# Sensor_board_2024.net
KiCad netlist of a schematic drawn in EAGLE
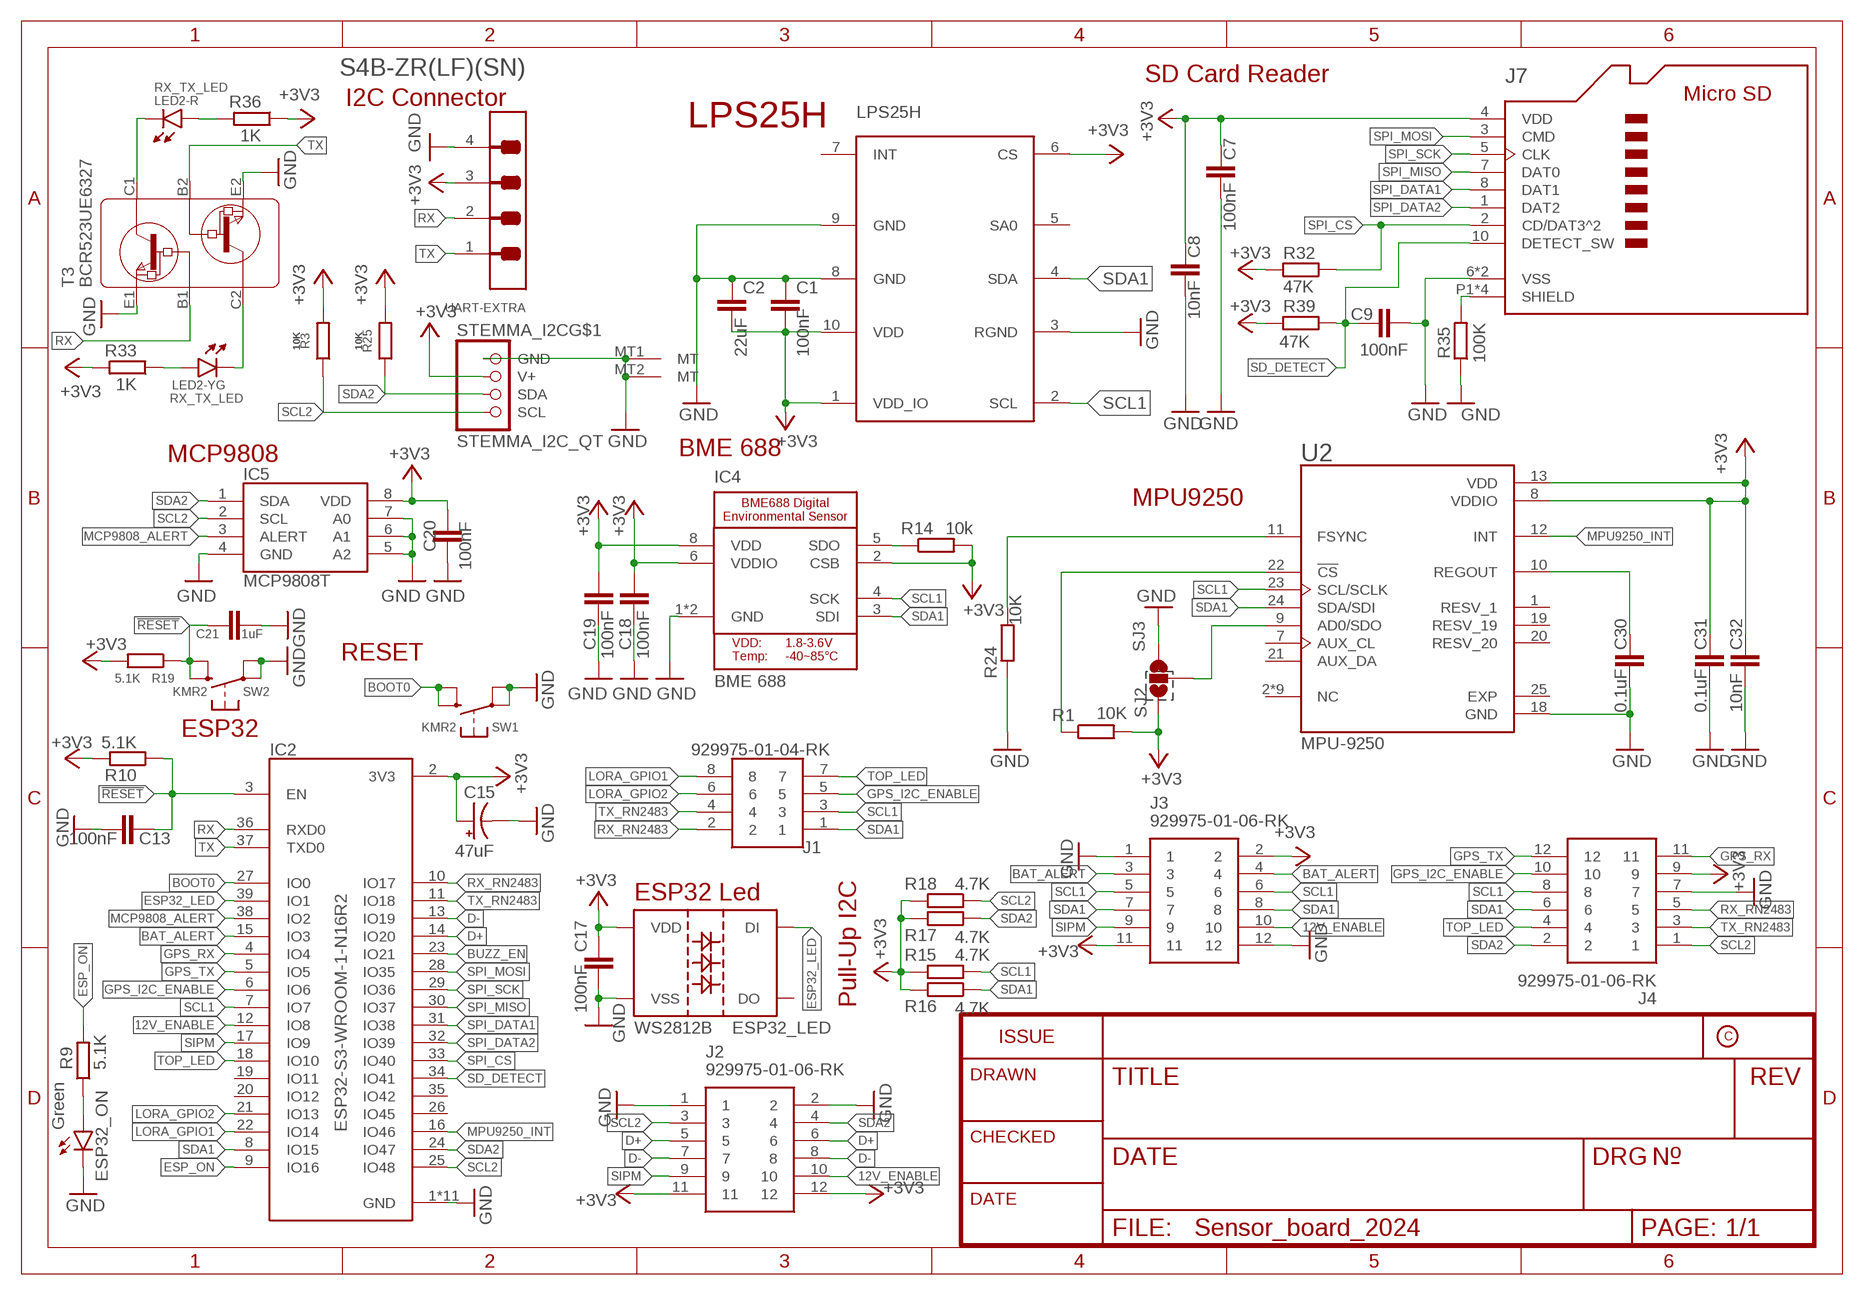
[diagram p0: schematic, sheet 1]

(export (version "E")
  (design (tool "Eeschema 10.0.6"))
  (components
    (comp (ref "C1")
      (value "100nF")
      (footprint "eagle-import:C0603")
      (libsource (lib "eagle-import") (part "C-EUC0603"))
    )
    (comp (ref "C2")
      (value "22uF")
      (footprint "eagle-import:C0603")
      (libsource (lib "eagle-import") (part "C-EUC0603"))
    )
    (comp (ref "C7")
      (value "100nF")
      (footprint "eagle-import:C0603")
      (libsource (lib "eagle-import") (part "C-EUC0603"))
    )
    (comp (ref "C8")
      (value "10nF")
      (footprint "eagle-import:C0603")
      (libsource (lib "eagle-import") (part "C-EUC0603"))
    )
    (comp (ref "C9")
      (value "100nF")
      (footprint "eagle-import:C0603")
      (libsource (lib "eagle-import") (part "C-EUC0603"))
    )
    (comp (ref "C13")
      (value "100nF")
      (footprint "eagle-import:C0603")
      (libsource (lib "eagle-import") (part "C-EUC0603"))
    )
    (comp (ref "C15")
      (value "47uF")
      (footprint "eagle-import:CAPMP6032X250N")
      (fields (field (name "MF") "Vishay") (field (name "MP") "293D226X9025C2TE3"))
      (libsource (lib "eagle-import") (part "293D226X9025C2TE3"))
    )
    (comp (ref "C17")
      (value "100nF")
      (footprint "eagle-import:C0603")
      (libsource (lib "eagle-import") (part "C-EUC0603"))
    )
    (comp (ref "C18")
      (value "100nF")
      (footprint "eagle-import:C0603")
      (libsource (lib "eagle-import") (part "C-EUC0603"))
    )
    (comp (ref "C19")
      (value "100nF")
      (footprint "eagle-import:C0603")
      (libsource (lib "eagle-import") (part "C-EUC0603"))
    )
    (comp (ref "C20")
      (value "100nF")
      (footprint "eagle-import:C0603")
      (libsource (lib "eagle-import") (part "C-EUC0603"))
    )
    (comp (ref "C21")
      (value "1uF")
      (footprint "eagle-import:C0603")
      (libsource (lib "eagle-import") (part "C-EUC0603"))
    )
    (comp (ref "C30")
      (value "0.1uF")
      (footprint "eagle-import:0603-CAP")
      (libsource (lib "eagle-import") (part "0.1UF-25V(+80/-20%)(0603)"))
    )
    (comp (ref "C31")
      (value "0.1uF")
      (footprint "eagle-import:0603-CAP")
      (libsource (lib "eagle-import") (part "0.1UF-25V(+80/-20%)(0603)"))
    )
    (comp (ref "C32")
      (value "10nF")
      (footprint "eagle-import:0603-CAP")
      (libsource (lib "eagle-import") (part "0.1UF-25V(+80/-20%)(0603)"))
    )
    (comp (ref "ESP32_LED")
      (value "WS2812B")
      (footprint "eagle-import:WS2812B")
      (libsource (lib "eagle-import") (part "WS2812B"))
    )
    (comp (ref "ESP32_ON")
      (value "Green")
      (footprint "eagle-import:CHIPLED_0805")
      (libsource (lib "eagle-import") (part "LEDCHIPLED_0805"))
    )
    (comp (ref "IC2")
      (value "ESP32-S3-WROOM-1-N16R2")
      (footprint "eagle-import:XCVR_ESP32-S3-WROOM-1-N16R2")
      (fields (field (name "MF") "Espressif Systems") (field (name "SPICEPREFIX") "X"))
      (libsource (lib "eagle-import") (part "ESP32-S3-WROOM-1-N16R2"))
    )
    (comp (ref "IC4")
      (value "BME 688")
      (footprint "eagle-import:BME_688")
      (libsource (lib "eagle-import") (part "BME_688_V1"))
    )
    (comp (ref "IC5")
      (value "MCP9808T")
      (footprint "eagle-import:SOP65P490X110-8N")
      (fields
        (field (name "MANUFACTURER_PART_NUMBER") "MCP9808T-E/MS")
        (field (name "MOUSER_PART_NUMBER") "579-MCP9808T-E/MS")
      )
      (libsource (lib "eagle-import") (part "MCP9808T-E_MS"))
    )
    (comp (ref "J1")
      (value "929975-01-04-RK")
      (footprint "eagle-import:RHDR8W76P254_2X4_1016X508X839P")
      (fields (field (name "MOUSER_PART_NUMBER") "517-929975-01-04-RK"))
      (libsource (lib "eagle-import") (part "929975-01-04-RK"))
    )
    (comp (ref "J2")
      (value "929975-01-06-RK")
      (footprint "eagle-import:RHDR12W76P254_2X6_1524X508X839")
      (fields (field (name "MOUSER_PART_NUMBER") "517-929975-01-06-RK"))
      (libsource (lib "eagle-import") (part "929975-01-06-RK"))
    )
    (comp (ref "J3")
      (value "929975-01-06-RK")
      (footprint "eagle-import:RHDR12W76P254_2X6_1524X508X839")
      (fields (field (name "MOUSER_PART_NUMBER") "517-929975-01-06-RK"))
      (libsource (lib "eagle-import") (part "929975-01-06-RK"))
    )
    (comp (ref "J4")
      (value "929975-01-06-RK")
      (footprint "eagle-import:RHDR12W76P254_2X6_1524X508X839")
      (fields (field (name "MOUSER_PART_NUMBER") "517-929975-01-06-RK"))
      (libsource (lib "eagle-import") (part "929975-01-06-RK"))
    )
    (comp (ref "J7")
      (value "503398-1892")
      (footprint "eagle-import:MOLEX_503398-1892")
      (fields (field (name "MF") "Molex") (field (name "MP") "5033981892"))
      (libsource (lib "eagle-import") (part "503398-1892"))
    )
    (comp (ref "LED2")
      (value "RX_TX_LED")
      (footprint "eagle-import:3216(1206)-4")
      (fields (field (name "MF") "OptoSupply") (field (name "MP") "OSRG1206C1C"))
      (libsource (lib "eagle-import") (part "OSRG1206C1C"))
    )
    (comp (ref "LPS25H")
      (value "LPS25H")
      (footprint "eagle-import:LPS25H")
      (fields (field (name "MF") "STMicroelectronics"))
      (libsource (lib "eagle-import") (part "LPS25H"))
    )
    (comp (ref "R1")
      (value "10K")
      (footprint "eagle-import:R0603")
      (libsource (lib "eagle-import") (part "rcl_334_R-EU_R0603"))
    )
    (comp (ref "R3")
      (value "10K")
      (footprint "eagle-import:R0603")
      (libsource (lib "eagle-import") (part "rcl_334_R-EU_R0603"))
    )
    (comp (ref "R9")
      (value "5.1K")
      (footprint "eagle-import:R0603")
      (libsource (lib "eagle-import") (part "rcl_334_R-EU_R0603"))
    )
    (comp (ref "R10")
      (value "5.1K")
      (footprint "eagle-import:R0603")
      (libsource (lib "eagle-import") (part "rcl_334_R-EU_R0603"))
    )
    (comp (ref "R14")
      (value "10k")
      (footprint "eagle-import:R0603")
      (libsource (lib "eagle-import") (part "rcl_334_R-EU_R0603"))
    )
    (comp (ref "R15")
      (value "4.7K")
      (footprint "eagle-import:R0603")
      (libsource (lib "eagle-import") (part "rcl_334_R-EU_R0603"))
    )
    (comp (ref "R16")
      (value "4.7K")
      (footprint "eagle-import:R0603")
      (libsource (lib "eagle-import") (part "rcl_334_R-EU_R0603"))
    )
    (comp (ref "R17")
      (value "4.7K")
      (footprint "eagle-import:R0603")
      (libsource (lib "eagle-import") (part "rcl_334_R-EU_R0603"))
    )
    (comp (ref "R18")
      (value "4.7K")
      (footprint "eagle-import:R0603")
      (libsource (lib "eagle-import") (part "rcl_334_R-EU_R0603"))
    )
    (comp (ref "R19")
      (value "5.1K")
      (footprint "eagle-import:R0603")
      (libsource (lib "eagle-import") (part "rcl_334_R-EU_R0603"))
    )
    (comp (ref "R24")
      (value "10K")
      (footprint "eagle-import:R0603")
      (libsource (lib "eagle-import") (part "rcl_334_R-EU_R0603"))
    )
    (comp (ref "R25")
      (value "10K")
      (footprint "eagle-import:R0603")
      (libsource (lib "eagle-import") (part "rcl_334_R-EU_R0603"))
    )
    (comp (ref "R32")
      (value "47K")
      (footprint "eagle-import:R0603")
      (libsource (lib "eagle-import") (part "R-EU_R0603"))
    )
    (comp (ref "R33")
      (value "1K")
      (footprint "eagle-import:R0603")
      (libsource (lib "eagle-import") (part "R-EU_R0603"))
    )
    (comp (ref "R35")
      (value "100K")
      (footprint "eagle-import:R0603")
      (libsource (lib "eagle-import") (part "R-EU_R0603"))
    )
    (comp (ref "R36")
      (value "1K")
      (footprint "eagle-import:R0603")
      (libsource (lib "eagle-import") (part "R-EU_R0603"))
    )
    (comp (ref "R39")
      (value "47K")
      (footprint "eagle-import:R0603")
      (libsource (lib "eagle-import") (part "R-EU_R0603"))
    )
    (comp (ref "SJ2")
      (value "SJ3")
      (footprint "eagle-import:SPARKFUN_SJ_3")
      (libsource (lib "eagle-import") (part "SPARKFUN_SOLDERJUMPER_2WAYS"))
    )
    (comp (ref "STEMMA_I2C")
      (value "STEMMA_I2C_QT")
      (footprint "eagle-import:JST_SH4")
      (libsource (lib "eagle-import") (part "STEMMA_I2C_QT"))
    )
    (comp (ref "SW1")
      (value "KMR2")
      (footprint "eagle-import:BTN_KMR2_4.6X2.8")
      (libsource (lib "eagle-import") (part "SWITCH_TACT_SMT4.6X2.8"))
    )
    (comp (ref "SW2")
      (value "KMR2")
      (footprint "eagle-import:BTN_KMR2_4.6X2.8")
      (libsource (lib "eagle-import") (part "SWITCH_TACT_SMT4.6X2.8"))
    )
    (comp (ref "T3")
      (value "BCR523UE6327")
      (footprint "eagle-import:SOT-23")
      (fields (field (name "MPN") "DSS20201L-7"))
      (libsource (lib "eagle-import") (part "NPNSOT23"))
    )
    (comp (ref "U2")
      (value "MPU-9250")
      (footprint "eagle-import:QFN40P300X300X105-25N")
      (fields (field (name "MF") "TDK InvenSense"))
      (libsource (lib "eagle-import") (part "MPU-9250"))
    )
    (comp (ref "UART-EXTRA")
      (value "JST_S4B-ZR_LF")
      (footprint "eagle-import:JST_S4B-ZR_LF_SN_0")
      (fields
        (field (name "DIGIKEY_PART_NUMBER") "455-1671-ND")
        (field (name "MF") "JST")
        (field (name "MPN") "S4B-ZR(LF)(SN)")
      )
      (libsource (lib "eagle-import") (part "JST_S4B-ZR_LF_SNJST_S4B-ZR_LF_SN_0_0"))
    )
  )
  (nets
    (net (code "1") (name "+3V3") (class "Default")
      (node (ref "C1") (pin "2") (pinfunction "2_2") (pintype "passive"))
      (node (ref "C15") (pin "1") (pinfunction "+_1") (pintype "passive"))
      (node (ref "C17") (pin "1") (pinfunction "1_1") (pintype "passive"))
      (node (ref "C18") (pin "2") (pinfunction "2_2") (pintype "passive"))
      (node (ref "C19") (pin "2") (pinfunction "2_2") (pintype "passive"))
      (node (ref "C2") (pin "2") (pinfunction "2_2") (pintype "passive"))
      (node (ref "C20") (pin "2") (pinfunction "2_2") (pintype "passive"))
      (node (ref "C31") (pin "1") (pinfunction "1_1") (pintype "passive"))
      (node (ref "C32") (pin "1") (pinfunction "1_1") (pintype "passive"))
      (node (ref "C7") (pin "1") (pinfunction "1_1") (pintype "passive"))
      (node (ref "C8") (pin "1") (pinfunction "1_1") (pintype "passive"))
      (node (ref "ESP32_LED") (pin "1") (pinfunction "VDD_1") (pintype "bidirectional"))
      (node (ref "IC2") (pin "2") (pinfunction "3V3_2") (pintype "power_in"))
      (node (ref "IC4") (pin "2") (pinfunction "CSB_2") (pintype "input"))
      (node (ref "IC4") (pin "6") (pinfunction "VDDIO_6") (pintype "power_in"))
      (node (ref "IC4") (pin "8") (pinfunction "VDD_8") (pintype "power_in"))
      (node (ref "IC5") (pin "8") (pinfunction "VDD_8") (pintype "power_in"))
      (node (ref "J2") (pin "11") (pinfunction "11_11") (pintype "bidirectional"))
      (node (ref "J2") (pin "12") (pinfunction "12_12") (pintype "bidirectional"))
      (node (ref "J3") (pin "11") (pinfunction "11_11") (pintype "bidirectional"))
      (node (ref "J3") (pin "2") (pinfunction "2_2") (pintype "bidirectional"))
      (node (ref "J4") (pin "9") (pinfunction "9_9") (pintype "bidirectional"))
      (node (ref "J7") (pin "4") (pinfunction "VDD_4") (pintype "bidirectional"))
      (node (ref "LPS25H") (pin "1") (pinfunction "VDD_IO_1") (pintype "power_in"))
      (node (ref "LPS25H") (pin "10") (pinfunction "VDD_10") (pintype "power_in"))
      (node (ref "LPS25H") (pin "6") (pinfunction "CS_6") (pintype "bidirectional"))
      (node (ref "R1") (pin "2") (pinfunction "2_2") (pintype "passive"))
      (node (ref "R10") (pin "2") (pinfunction "2_2") (pintype "passive"))
      (node (ref "R14") (pin "2") (pinfunction "2_2") (pintype "passive"))
      (node (ref "R15") (pin "2") (pinfunction "2_2") (pintype "passive"))
      (node (ref "R16") (pin "2") (pinfunction "2_2") (pintype "passive"))
      (node (ref "R17") (pin "2") (pinfunction "2_2") (pintype "passive"))
      (node (ref "R18") (pin "2") (pinfunction "2_2") (pintype "passive"))
      (node (ref "R19") (pin "2") (pinfunction "2_2") (pintype "passive"))
      (node (ref "R25") (pin "2") (pinfunction "2_2") (pintype "passive"))
      (node (ref "R3") (pin "2") (pinfunction "2_2") (pintype "passive"))
      (node (ref "R32") (pin "2") (pinfunction "2_2") (pintype "passive"))
      (node (ref "R33") (pin "2") (pinfunction "2_2") (pintype "passive"))
      (node (ref "R36") (pin "1") (pinfunction "1_1") (pintype "passive"))
      (node (ref "R39") (pin "2") (pinfunction "2_2") (pintype "passive"))
      (node (ref "SJ2") (pin "1") (pinfunction "1_1") (pintype "passive"))
      (node (ref "STEMMA_I2C") (pin "2") (pinfunction "V+_2") (pintype "passive"))
      (node (ref "U2") (pin "13") (pinfunction "VDD_13") (pintype "power_in"))
      (node (ref "U2") (pin "8") (pinfunction "VDDIO_8") (pintype "power_in"))
      (node (ref "UART-EXTRA") (pin "3") (pinfunction "3_3") (pintype "passive"))
    )
    (net (code "2") (name "/RESV_1") (class "Default")
      (node (ref "U2") (pin "1") (pinfunction "RESV_1_1") (pintype "power_in"))
    )
    (net (code "3") (name "/RESV_20") (class "Default")
      (node (ref "U2") (pin "20") (pinfunction "RESV_20_20") (pintype "power_in"))
    )
    (net (code "4") (name "/~{RESET}") (class "Default")
      (node (ref "C13") (pin "1") (pinfunction "1_1") (pintype "passive"))
      (node (ref "C21") (pin "1") (pinfunction "1_1") (pintype "passive"))
      (node (ref "IC2") (pin "3") (pinfunction "EN_3") (pintype "input"))
      (node (ref "R10") (pin "1") (pinfunction "1_1") (pintype "passive"))
      (node (ref "R19") (pin "1") (pinfunction "1_1") (pintype "passive"))
      (node (ref "SW2") (pin "B") (pinfunction "S_B") (pintype "passive"))
      (node (ref "SW2") (pin "B'") (pinfunction "S1_B'") (pintype "passive"))
    )
    (net (code "5") (name "12V_ENABLE") (class "Default")
      (node (ref "IC2") (pin "12") (pinfunction "IO8_12") (pintype "bidirectional"))
      (node (ref "J2") (pin "10") (pinfunction "10_10") (pintype "bidirectional"))
      (node (ref "J3") (pin "10") (pinfunction "10_10") (pintype "bidirectional"))
    )
    (net (code "6") (name "BAT_ALERT") (class "Default")
      (node (ref "IC2") (pin "15") (pinfunction "IO3_15") (pintype "bidirectional"))
      (node (ref "J3") (pin "3") (pinfunction "3_3") (pintype "bidirectional"))
      (node (ref "J3") (pin "4") (pinfunction "4_4") (pintype "bidirectional"))
    )
    (net (code "7") (name "BOOT0") (class "Default")
      (node (ref "IC2") (pin "27") (pinfunction "IO0_27") (pintype "bidirectional"))
      (node (ref "SW1") (pin "B") (pinfunction "S_B") (pintype "passive"))
      (node (ref "SW1") (pin "B'") (pinfunction "S1_B'") (pintype "passive"))
    )
    (net (code "8") (name "BUZZ_EN") (class "Default")
      (node (ref "IC2") (pin "23") (pinfunction "IO21_23") (pintype "bidirectional"))
    )
    (net (code "9") (name "D+") (class "Default")
      (node (ref "IC2") (pin "14") (pinfunction "IO20_14") (pintype "bidirectional"))
      (node (ref "J2") (pin "5") (pinfunction "5_5") (pintype "bidirectional"))
      (node (ref "J2") (pin "6") (pinfunction "6_6") (pintype "bidirectional"))
    )
    (net (code "10") (name "D-") (class "Default")
      (node (ref "IC2") (pin "13") (pinfunction "IO19_13") (pintype "bidirectional"))
      (node (ref "J2") (pin "7") (pinfunction "7_7") (pintype "bidirectional"))
      (node (ref "J2") (pin "8") (pinfunction "8_8") (pintype "bidirectional"))
    )
    (net (code "11") (name "ESP32_LED") (class "Default")
      (node (ref "ESP32_LED") (pin "4") (pinfunction "DI_4") (pintype "bidirectional"))
      (node (ref "IC2") (pin "39") (pinfunction "IO1_39") (pintype "bidirectional"))
    )
    (net (code "12") (name "ESP_ON") (class "Default")
      (node (ref "IC2") (pin "9") (pinfunction "IO16_9") (pintype "bidirectional"))
      (node (ref "R9") (pin "2") (pinfunction "2_2") (pintype "passive"))
    )
    (net (code "13") (name "GND") (class "Default")
      (node (ref "C1") (pin "1") (pinfunction "1_1") (pintype "passive"))
      (node (ref "C13") (pin "2") (pinfunction "2_2") (pintype "passive"))
      (node (ref "C15") (pin "2") (pinfunction "-_2") (pintype "passive"))
      (node (ref "C17") (pin "2") (pinfunction "2_2") (pintype "passive"))
      (node (ref "C18") (pin "1") (pinfunction "1_1") (pintype "passive"))
      (node (ref "C19") (pin "1") (pinfunction "1_1") (pintype "passive"))
      (node (ref "C2") (pin "1") (pinfunction "1_1") (pintype "passive"))
      (node (ref "C20") (pin "1") (pinfunction "1_1") (pintype "passive"))
      (node (ref "C21") (pin "2") (pinfunction "2_2") (pintype "passive"))
      (node (ref "C30") (pin "2") (pinfunction "2_2") (pintype "passive"))
      (node (ref "C31") (pin "2") (pinfunction "2_2") (pintype "passive"))
      (node (ref "C32") (pin "2") (pinfunction "2_2") (pintype "passive"))
      (node (ref "C7") (pin "2") (pinfunction "2_2") (pintype "passive"))
      (node (ref "C8") (pin "2") (pinfunction "2_2") (pintype "passive"))
      (node (ref "C9") (pin "2") (pinfunction "2_2") (pintype "passive"))
      (node (ref "ESP32_LED") (pin "3") (pinfunction "VSS_3") (pintype "bidirectional"))
      (node (ref "ESP32_ON") (pin "C") (pinfunction "C_C") (pintype "passive"))
      (node (ref "IC2") (pin "1") (pinfunction "GND_1") (pintype "power_in"))
      (node (ref "IC2") (pin "40") (pinfunction "GND_40") (pintype "power_in"))
      (node (ref "IC2") (pin "41_1") (pinfunction "GND_41_1") (pintype "power_in"))
      (node (ref "IC2") (pin "41_2") (pinfunction "GND_41_2") (pintype "power_in"))
      (node (ref "IC2") (pin "41_3") (pinfunction "GND_41_3") (pintype "power_in"))
      (node (ref "IC2") (pin "41_4") (pinfunction "GND_41_4") (pintype "power_in"))
      (node (ref "IC2") (pin "41_5") (pinfunction "GND_41_5") (pintype "power_in"))
      (node (ref "IC2") (pin "41_6") (pinfunction "GND_41_6") (pintype "power_in"))
      (node (ref "IC2") (pin "41_7") (pinfunction "GND_41_7") (pintype "power_in"))
      (node (ref "IC2") (pin "41_8") (pinfunction "GND_41_8") (pintype "power_in"))
      (node (ref "IC2") (pin "41_9") (pinfunction "GND_41_9") (pintype "power_in"))
      (node (ref "IC4") (pin "1") (pinfunction "GND_1") (pintype "power_in"))
      (node (ref "IC4") (pin "7") (pinfunction "GND_7") (pintype "power_in"))
      (node (ref "IC5") (pin "4") (pinfunction "GND_4") (pintype "power_in"))
      (node (ref "IC5") (pin "5") (pinfunction "A2_5") (pintype "input"))
      (node (ref "IC5") (pin "6") (pinfunction "A1_6") (pintype "input"))
      (node (ref "IC5") (pin "7") (pinfunction "A0_7") (pintype "input"))
      (node (ref "J2") (pin "1") (pinfunction "1_1") (pintype "bidirectional"))
      (node (ref "J2") (pin "2") (pinfunction "2_2") (pintype "bidirectional"))
      (node (ref "J3") (pin "1") (pinfunction "1_1") (pintype "bidirectional"))
      (node (ref "J3") (pin "12") (pinfunction "12_12") (pintype "bidirectional"))
      (node (ref "J4") (pin "7") (pinfunction "7_7") (pintype "bidirectional"))
      (node (ref "J7") (pin "6") (pinfunction "VSS_6") (pintype "bidirectional"))
      (node (ref "J7") (pin "9") (pinfunction "VSS_9") (pintype "bidirectional"))
      (node (ref "LPS25H") (pin "3") (pinfunction "RGND_3") (pintype "bidirectional"))
      (node (ref "LPS25H") (pin "8") (pinfunction "GND_8") (pintype "power_in"))
      (node (ref "LPS25H") (pin "9") (pinfunction "GND_9") (pintype "power_in"))
      (node (ref "R24") (pin "1") (pinfunction "1_1") (pintype "passive"))
      (node (ref "R35") (pin "1") (pinfunction "1_1") (pintype "passive"))
      (node (ref "SJ2") (pin "3") (pinfunction "3_3") (pintype "passive"))
      (node (ref "STEMMA_I2C") (pin "1") (pinfunction "GND_1") (pintype "passive"))
      (node (ref "STEMMA_I2C") (pin "MT1") (pinfunction "MT_MT1") (pintype "bidirectional"))
      (node (ref "STEMMA_I2C") (pin "MT2") (pinfunction "MT_MT2") (pintype "bidirectional"))
      (node (ref "SW1") (pin "A") (pinfunction "P_A") (pintype "passive"))
      (node (ref "SW1") (pin "A'") (pinfunction "P1_A'") (pintype "passive"))
      (node (ref "SW2") (pin "A") (pinfunction "P_A") (pintype "passive"))
      (node (ref "SW2") (pin "A'") (pinfunction "P1_A'") (pintype "passive"))
      (node (ref "T3") (pin "E1") (pinfunction "E1_E1") (pintype "passive"))
      (node (ref "T3") (pin "E2") (pinfunction "E2_E2") (pintype "passive"))
      (node (ref "U2") (pin "18") (pinfunction "GND_18") (pintype "power_in"))
      (node (ref "UART-EXTRA") (pin "4") (pinfunction "4_4") (pintype "passive"))
    )
    (net (code "14") (name "GPS_I2C_ENABLE") (class "Default")
      (node (ref "IC2") (pin "6") (pinfunction "IO6_6") (pintype "bidirectional"))
      (node (ref "J1") (pin "5") (pinfunction "5_5") (pintype "bidirectional"))
      (node (ref "J4") (pin "10") (pinfunction "10_10") (pintype "bidirectional"))
    )
    (net (code "15") (name "GPS_RX") (class "Default")
      (node (ref "IC2") (pin "4") (pinfunction "IO4_4") (pintype "bidirectional"))
      (node (ref "J4") (pin "11") (pinfunction "11_11") (pintype "bidirectional"))
    )
    (net (code "16") (name "GPS_TX") (class "Default")
      (node (ref "IC2") (pin "5") (pinfunction "IO5_5") (pintype "bidirectional"))
      (node (ref "J4") (pin "12") (pinfunction "12_12") (pintype "bidirectional"))
    )
    (net (code "17") (name "LORA_GPIO1") (class "Default")
      (node (ref "IC2") (pin "22") (pinfunction "IO14_22") (pintype "bidirectional"))
      (node (ref "J1") (pin "8") (pinfunction "8_8") (pintype "bidirectional"))
    )
    (net (code "18") (name "LORA_GPIO2") (class "Default")
      (node (ref "IC2") (pin "21") (pinfunction "IO13_21") (pintype "bidirectional"))
      (node (ref "J1") (pin "6") (pinfunction "6_6") (pintype "bidirectional"))
    )
    (net (code "19") (name "MCP9808_ALERT") (class "Default")
      (node (ref "IC2") (pin "38") (pinfunction "IO2_38") (pintype "bidirectional"))
      (node (ref "IC5") (pin "3") (pinfunction "ALERT_3") (pintype "output"))
    )
    (net (code "20") (name "MPU9250_INT") (class "Default")
      (node (ref "IC2") (pin "16") (pinfunction "IO46_16") (pintype "bidirectional"))
      (node (ref "U2") (pin "12") (pinfunction "INT_12") (pintype "output"))
    )
    (net (code "21") (name "Net-(ESP32_ON-PadA)") (class "Default")
      (node (ref "ESP32_ON") (pin "A") (pinfunction "A_A") (pintype "passive"))
      (node (ref "R9") (pin "1") (pinfunction "1_1") (pintype "passive"))
    )
    (net (code "22") (name "Net-(IC4-SDO)") (class "Default")
      (node (ref "IC4") (pin "5") (pinfunction "SDO_5") (pintype "output"))
      (node (ref "R14") (pin "1") (pinfunction "1_1") (pintype "passive"))
    )
    (net (code "23") (name "Net-(J7-SHIELD-PadP1)") (class "Default")
      (node (ref "J7") (pin "P1") (pinfunction "SHIELD_P1") (pintype "bidirectional"))
      (node (ref "J7") (pin "P2") (pinfunction "SHIELD_P2") (pintype "bidirectional"))
      (node (ref "J7") (pin "P3") (pinfunction "SHIELD_P3") (pintype "bidirectional"))
      (node (ref "J7") (pin "P4") (pinfunction "SHIELD_P4") (pintype "bidirectional"))
      (node (ref "R35") (pin "2") (pinfunction "2_2") (pintype "passive"))
    )
    (net (code "24") (name "Net-(LED2A-A)") (class "Default")
      (node (ref "LED2") (pin "2") (pinfunction "A_2") (pintype "input"))
      (node (ref "R36") (pin "2") (pinfunction "2_2") (pintype "passive"))
    )
    (net (code "25") (name "Net-(LED2A-C)") (class "Default")
      (node (ref "LED2") (pin "1") (pinfunction "C_1") (pintype "output"))
      (node (ref "T3") (pin "C1") (pinfunction "C1_C1") (pintype "passive"))
    )
    (net (code "26") (name "Net-(LED2B-A)") (class "Default")
      (node (ref "LED2") (pin "4") (pinfunction "A_4") (pintype "input"))
      (node (ref "R33") (pin "1") (pinfunction "1_1") (pintype "passive"))
    )
    (net (code "27") (name "Net-(LED2B-C)") (class "Default")
      (node (ref "LED2") (pin "3") (pinfunction "C_3") (pintype "output"))
      (node (ref "T3") (pin "C2") (pinfunction "C2_C2") (pintype "passive"))
    )
    (net (code "28") (name "Net-(U2-AD0{slash}SDO)") (class "Default")
      (node (ref "SJ2") (pin "2") (pinfunction "2_2") (pintype "passive"))
      (node (ref "U2") (pin "9") (pinfunction "AD0/SDO_9") (pintype "output"))
    )
    (net (code "29") (name "Net-(U2-FSYNC)") (class "Default")
      (node (ref "R24") (pin "2") (pinfunction "2_2") (pintype "passive"))
      (node (ref "U2") (pin "11") (pinfunction "FSYNC_11") (pintype "input"))
    )
    (net (code "30") (name "Net-(U2-REGOUT)") (class "Default")
      (node (ref "C30") (pin "1") (pinfunction "1_1") (pintype "passive"))
      (node (ref "U2") (pin "10") (pinfunction "REGOUT_10") (pintype "output"))
    )
    (net (code "31") (name "Net-(U2-~{CS})") (class "Default")
      (node (ref "R1") (pin "1") (pinfunction "1_1") (pintype "passive"))
      (node (ref "U2") (pin "22") (pinfunction "~{CS}_22") (pintype "input"))
    )
    (net (code "32") (name "RX") (class "Default")
      (node (ref "IC2") (pin "36") (pinfunction "RXD0_36") (pintype "bidirectional"))
      (node (ref "T3") (pin "B1") (pinfunction "B1_B1") (pintype "passive"))
      (node (ref "UART-EXTRA") (pin "2") (pinfunction "2_2") (pintype "passive"))
    )
    (net (code "33") (name "RX_RN2483") (class "Default")
      (node (ref "IC2") (pin "10") (pinfunction "IO17_10") (pintype "bidirectional"))
      (node (ref "J1") (pin "2") (pinfunction "2_2") (pintype "bidirectional"))
      (node (ref "J4") (pin "5") (pinfunction "5_5") (pintype "bidirectional"))
    )
    (net (code "34") (name "SCL1") (class "Default")
      (node (ref "IC2") (pin "7") (pinfunction "IO7_7") (pintype "bidirectional"))
      (node (ref "IC4") (pin "4") (pinfunction "SCK_4") (pintype "input"))
      (node (ref "J1") (pin "3") (pinfunction "3_3") (pintype "bidirectional"))
      (node (ref "J3") (pin "5") (pinfunction "5_5") (pintype "bidirectional"))
      (node (ref "J3") (pin "6") (pinfunction "6_6") (pintype "bidirectional"))
      (node (ref "J4") (pin "8") (pinfunction "8_8") (pintype "bidirectional"))
      (node (ref "LPS25H") (pin "2") (pinfunction "SCL_2") (pintype "bidirectional"))
      (node (ref "R15") (pin "1") (pinfunction "1_1") (pintype "passive"))
      (node (ref "U2") (pin "23") (pinfunction "SCL/SCLK_23") (pintype "input"))
    )
    (net (code "35") (name "SCL2") (class "Default")
      (node (ref "IC2") (pin "25") (pinfunction "IO48_25") (pintype "bidirectional"))
      (node (ref "IC5") (pin "2") (pinfunction "SCL_2") (pintype "input"))
      (node (ref "J2") (pin "3") (pinfunction "3_3") (pintype "bidirectional"))
      (node (ref "J4") (pin "1") (pinfunction "1_1") (pintype "bidirectional"))
      (node (ref "R18") (pin "1") (pinfunction "1_1") (pintype "passive"))
      (node (ref "R3") (pin "1") (pinfunction "1_1") (pintype "passive"))
      (node (ref "STEMMA_I2C") (pin "4") (pinfunction "SCL_4") (pintype "passive"))
    )
    (net (code "36") (name "SDA1") (class "Default")
      (node (ref "IC2") (pin "8") (pinfunction "IO15_8") (pintype "bidirectional"))
      (node (ref "IC4") (pin "3") (pinfunction "SDI_3") (pintype "input"))
      (node (ref "J1") (pin "1") (pinfunction "1_1") (pintype "bidirectional"))
      (node (ref "J3") (pin "7") (pinfunction "7_7") (pintype "bidirectional"))
      (node (ref "J3") (pin "8") (pinfunction "8_8") (pintype "bidirectional"))
      (node (ref "J4") (pin "6") (pinfunction "6_6") (pintype "bidirectional"))
      (node (ref "LPS25H") (pin "4") (pinfunction "SDA_4") (pintype "bidirectional"))
      (node (ref "R16") (pin "1") (pinfunction "1_1") (pintype "passive"))
      (node (ref "U2") (pin "24") (pinfunction "SDA/SDI_24") (pintype "bidirectional"))
    )
    (net (code "37") (name "SDA2") (class "Default")
      (node (ref "IC2") (pin "24") (pinfunction "IO47_24") (pintype "bidirectional"))
      (node (ref "IC5") (pin "1") (pinfunction "SDA_1") (pintype "bidirectional"))
      (node (ref "J2") (pin "4") (pinfunction "4_4") (pintype "bidirectional"))
      (node (ref "J4") (pin "2") (pinfunction "2_2") (pintype "bidirectional"))
      (node (ref "R17") (pin "1") (pinfunction "1_1") (pintype "passive"))
      (node (ref "R25") (pin "1") (pinfunction "1_1") (pintype "passive"))
      (node (ref "STEMMA_I2C") (pin "3") (pinfunction "SDA_3") (pintype "passive"))
    )
    (net (code "38") (name "SD_DETECT") (class "Default")
      (node (ref "C9") (pin "1") (pinfunction "1_1") (pintype "passive"))
      (node (ref "IC2") (pin "34") (pinfunction "IO41_34") (pintype "bidirectional"))
      (node (ref "J7") (pin "10") (pinfunction "DETECT_SW_10") (pintype "bidirectional"))
      (node (ref "R39") (pin "1") (pinfunction "1_1") (pintype "passive"))
    )
    (net (code "39") (name "SIPM") (class "Default")
      (node (ref "IC2") (pin "17") (pinfunction "IO9_17") (pintype "bidirectional"))
      (node (ref "J2") (pin "9") (pinfunction "9_9") (pintype "bidirectional"))
      (node (ref "J3") (pin "9") (pinfunction "9_9") (pintype "bidirectional"))
    )
    (net (code "40") (name "SPI_CS") (class "Default")
      (node (ref "IC2") (pin "33") (pinfunction "IO40_33") (pintype "bidirectional"))
      (node (ref "J7") (pin "2") (pinfunction "CD/DAT3^2_2") (pintype "bidirectional"))
      (node (ref "R32") (pin "1") (pinfunction "1_1") (pintype "passive"))
    )
    (net (code "41") (name "SPI_DATA1") (class "Default")
      (node (ref "IC2") (pin "31") (pinfunction "IO38_31") (pintype "bidirectional"))
      (node (ref "J7") (pin "8") (pinfunction "DAT1_8") (pintype "bidirectional"))
    )
    (net (code "42") (name "SPI_DATA2") (class "Default")
      (node (ref "IC2") (pin "32") (pinfunction "IO39_32") (pintype "bidirectional"))
      (node (ref "J7") (pin "1") (pinfunction "DAT2_1") (pintype "bidirectional"))
    )
    (net (code "43") (name "SPI_MISO") (class "Default")
      (node (ref "IC2") (pin "30") (pinfunction "IO37_30") (pintype "bidirectional"))
      (node (ref "J7") (pin "7") (pinfunction "DAT0_7") (pintype "bidirectional"))
    )
    (net (code "44") (name "SPI_MOSI") (class "Default")
      (node (ref "IC2") (pin "28") (pinfunction "IO35_28") (pintype "bidirectional"))
      (node (ref "J7") (pin "3") (pinfunction "CMD_3") (pintype "bidirectional"))
    )
    (net (code "45") (name "SPI_SCK") (class "Default")
      (node (ref "IC2") (pin "29") (pinfunction "IO36_29") (pintype "bidirectional"))
      (node (ref "J7") (pin "5") (pinfunction "CLK_5") (pintype "bidirectional"))
    )
    (net (code "46") (name "TOP_LED") (class "Default")
      (node (ref "IC2") (pin "18") (pinfunction "IO10_18") (pintype "bidirectional"))
      (node (ref "J1") (pin "7") (pinfunction "7_7") (pintype "bidirectional"))
      (node (ref "J4") (pin "4") (pinfunction "4_4") (pintype "bidirectional"))
    )
    (net (code "47") (name "TX") (class "Default")
      (node (ref "IC2") (pin "37") (pinfunction "TXD0_37") (pintype "bidirectional"))
      (node (ref "T3") (pin "B2") (pinfunction "B2_B2") (pintype "passive"))
      (node (ref "UART-EXTRA") (pin "1") (pinfunction "1_1") (pintype "passive"))
    )
    (net (code "48") (name "TX_RN2483") (class "Default")
      (node (ref "IC2") (pin "11") (pinfunction "IO18_11") (pintype "bidirectional"))
      (node (ref "J1") (pin "4") (pinfunction "4_4") (pintype "bidirectional"))
      (node (ref "J4") (pin "3") (pinfunction "3_3") (pintype "bidirectional"))
    )
    (net (code "49") (name "unconnected-(ESP32_LED-DO-Pad2)") (class "Default")
      (node (ref "ESP32_LED") (pin "2") (pinfunction "DO_2") (pintype "bidirectional"))
    )
    (net (code "50") (name "unconnected-(IC2-IO11-Pad19)") (class "Default")
      (node (ref "IC2") (pin "19") (pinfunction "IO11_19") (pintype "bidirectional"))
    )
    (net (code "51") (name "unconnected-(IC2-IO12-Pad20)") (class "Default")
      (node (ref "IC2") (pin "20") (pinfunction "IO12_20") (pintype "bidirectional"))
    )
    (net (code "52") (name "unconnected-(IC2-IO42-Pad35)") (class "Default")
      (node (ref "IC2") (pin "35") (pinfunction "IO42_35") (pintype "bidirectional"))
    )
    (net (code "53") (name "unconnected-(IC2-IO45-Pad26)") (class "Default")
      (node (ref "IC2") (pin "26") (pinfunction "IO45_26") (pintype "bidirectional"))
    )
    (net (code "54") (name "unconnected-(LPS25H-INT-Pad7)") (class "Default")
      (node (ref "LPS25H") (pin "7") (pinfunction "INT_7") (pintype "bidirectional"))
    )
    (net (code "55") (name "unconnected-(LPS25H-SA0-Pad5)") (class "Default")
      (node (ref "LPS25H") (pin "5") (pinfunction "SA0_5") (pintype "bidirectional"))
    )
    (net (code "56") (name "unconnected-(U2-AUX_CL-Pad7)") (class "Default")
      (node (ref "U2") (pin "7") (pinfunction "AUX_CL_7") (pintype "input"))
    )
    (net (code "57") (name "unconnected-(U2-AUX_DA-Pad21)") (class "Default")
      (node (ref "U2") (pin "21") (pinfunction "AUX_DA_21") (pintype "input"))
    )
    (net (code "58") (name "unconnected-(U2-EXP-Pad25)") (class "Default")
      (node (ref "U2") (pin "25") (pinfunction "EXP_25") (pintype "passive"))
    )
    (net (code "59") (name "unconnected-(U2-NC-Pad2)") (class "Default")
      (node (ref "U2") (pin "2") (pinfunction "NC_2") (pintype "no_connect"))
    )
    (net (code "60") (name "unconnected-(U2-NC-Pad3)") (class "Default")
      (node (ref "U2") (pin "3") (pinfunction "NC_3") (pintype "no_connect"))
    )
    (net (code "61") (name "unconnected-(U2-NC-Pad4)") (class "Default")
      (node (ref "U2") (pin "4") (pinfunction "NC_4") (pintype "no_connect"))
    )
    (net (code "62") (name "unconnected-(U2-NC-Pad5)") (class "Default")
      (node (ref "U2") (pin "5") (pinfunction "NC_5") (pintype "no_connect"))
    )
    (net (code "63") (name "unconnected-(U2-NC-Pad6)") (class "Default")
      (node (ref "U2") (pin "6") (pinfunction "NC_6") (pintype "no_connect"))
    )
    (net (code "64") (name "unconnected-(U2-NC-Pad14)") (class "Default")
      (node (ref "U2") (pin "14") (pinfunction "NC_14") (pintype "no_connect"))
    )
    (net (code "65") (name "unconnected-(U2-NC-Pad15)") (class "Default")
      (node (ref "U2") (pin "15") (pinfunction "NC_15") (pintype "no_connect"))
    )
    (net (code "66") (name "unconnected-(U2-NC-Pad16)") (class "Default")
      (node (ref "U2") (pin "16") (pinfunction "NC_16") (pintype "no_connect"))
    )
    (net (code "67") (name "unconnected-(U2-NC-Pad17)") (class "Default")
      (node (ref "U2") (pin "17") (pinfunction "NC_17") (pintype "no_connect"))
    )
    (net (code "68") (name "unconnected-(U2-RESV_19-Pad19)") (class "Default")
      (node (ref "U2") (pin "19") (pinfunction "RESV_19_19") (pintype "no_connect"))
    )
  )
)
